# Touch_Slider.net
KiCad netlist of a schematic drawn in Altium Designer
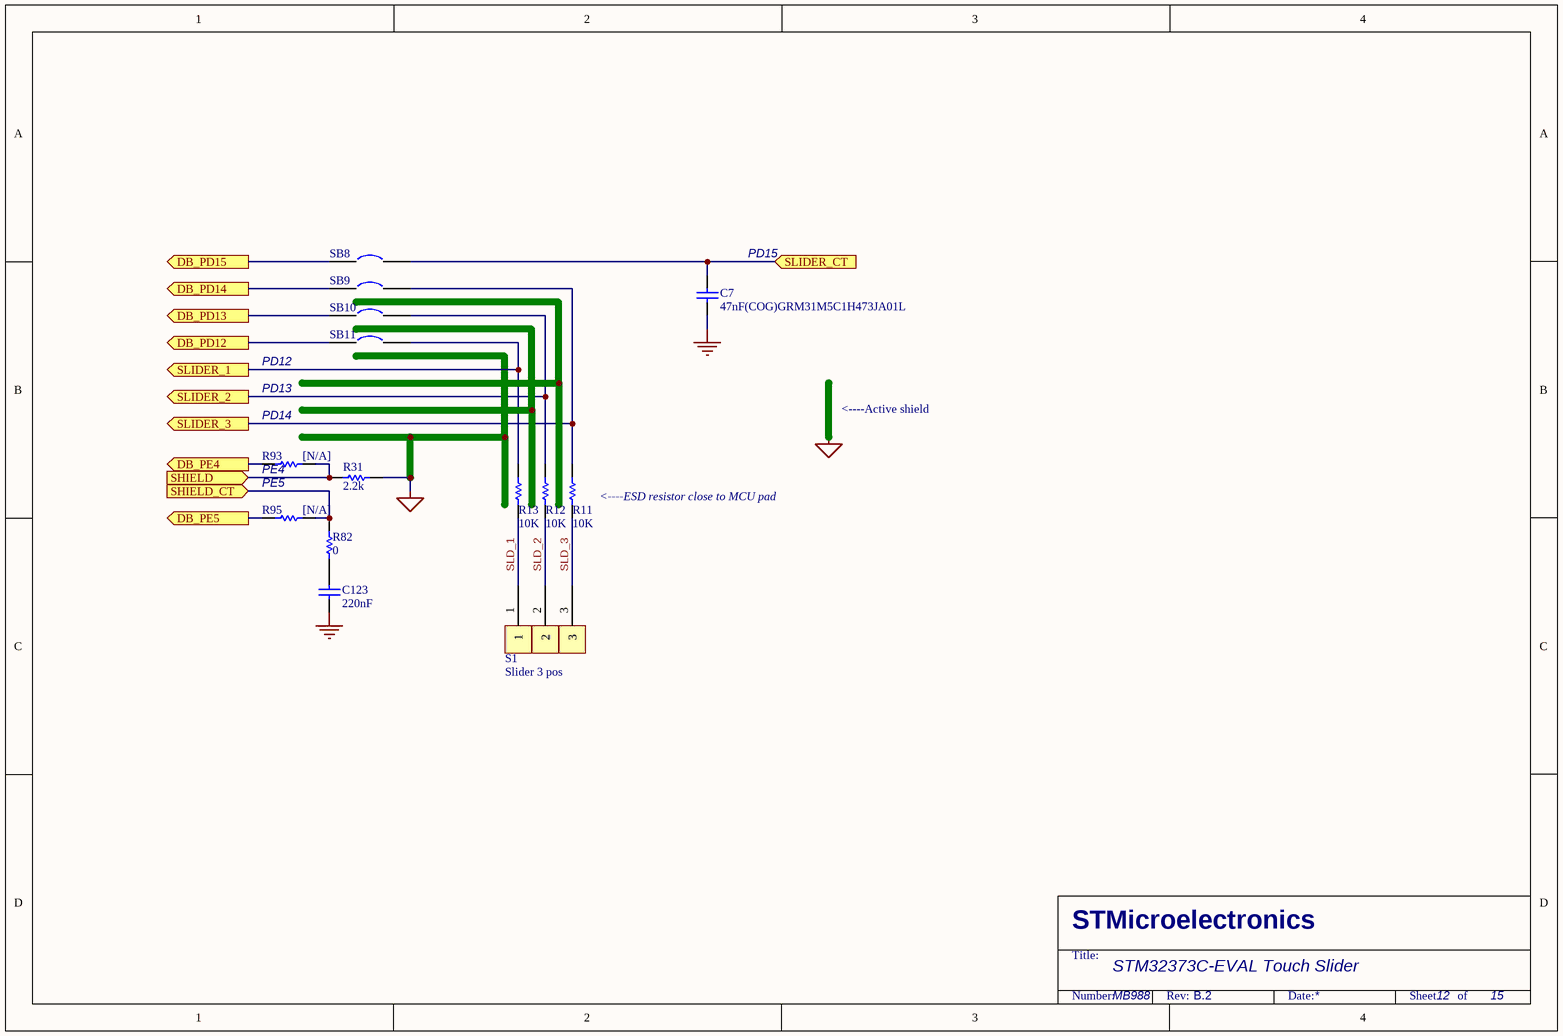
[diagram p0: Touch Slider.SchDoc]

(export (version "E")
  (design (tool "Eeschema 10.0.6"))
  (components
    (comp (ref "C7")
      (value "47nF(COG)GRM31M5C1H473JA01L")
      (footprint "1206C")
      (description "Capacitor")
      (fields (field (name "PUBLISHER") "Altium Limited"))
      (libsource (lib "Miscellaneous Devices") (part "CAP"))
    )
    (comp (ref "C123")
      (value "220nF")
      (footprint "0603C")
      (description "Capacitor")
      (fields (field (name "PUBLISHER") "Altium Limited"))
      (libsource (lib "Miscellaneous Devices") (part "CAP"))
    )
    (comp (ref "R11")
      (value "10K")
      (footprint "0603R")
      (description "Resistor")
      (fields (field (name "PUBLISHER") "Altium Limited"))
      (libsource (lib "Miscellaneous Devices") (part "res1"))
    )
    (comp (ref "R12")
      (value "10K")
      (footprint "0603R")
      (description "Resistor")
      (fields (field (name "PUBLISHER") "Altium Limited"))
      (libsource (lib "Miscellaneous Devices") (part "res1"))
    )
    (comp (ref "R13")
      (value "10K")
      (footprint "0603R")
      (description "Resistor")
      (fields (field (name "PUBLISHER") "Altium Limited"))
      (libsource (lib "Miscellaneous Devices") (part "res1"))
    )
    (comp (ref "R31")
      (value "2.2k")
      (footprint "0603R")
      (description "Resistor")
      (fields (field (name "PUBLISHER") "Altium Limited"))
      (libsource (lib "Miscellaneous Devices") (part "Res1"))
    )
    (comp (ref "R82")
      (value "0")
      (footprint "0603R")
      (description "Resistor")
      (fields (field (name "PUBLISHER") "Altium Limited"))
      (libsource (lib "Miscellaneous Devices") (part "Res1"))
    )
    (comp (ref "R93")
      (value "[N/A]")
      (footprint "0603R")
      (description "Resistor")
      (fields (field (name "PUBLISHER") "Altium Limited"))
      (libsource (lib "Miscellaneous Devices") (part "Res1"))
    )
    (comp (ref "R95")
      (value "[N/A]")
      (footprint "0603R")
      (description "Resistor")
      (fields (field (name "PUBLISHER") "Altium Limited"))
      (libsource (lib "Miscellaneous Devices") (part "Res1"))
    )
    (comp (ref "S1")
      (value "Slider 3 pos")
      (footprint "SLIDER3-2(50)")
      (description "plan de cuivre recouvert de vernis")
      (libsource (lib "MB963_1") (part "Slider 3 pos"))
    )
    (comp (ref "SB8")
      (value "~")
      (footprint "JP2_SMD")
      (description "Circuit Breaker")
      (fields (field (name "PUBLISHER") "Altium Limited"))
      (libsource (lib "Miscellaneous Devices") (part "Circuit Breaker"))
    )
    (comp (ref "SB9")
      (value "~")
      (footprint "JP2_SMD")
      (description "Circuit Breaker")
      (fields (field (name "PUBLISHER") "Altium Limited"))
      (libsource (lib "Miscellaneous Devices") (part "Circuit Breaker"))
    )
    (comp (ref "SB10")
      (value "~")
      (footprint "JP2_SMD")
      (description "Circuit Breaker")
      (fields (field (name "PUBLISHER") "Altium Limited"))
      (libsource (lib "Miscellaneous Devices") (part "Circuit Breaker"))
    )
    (comp (ref "SB11")
      (value "~")
      (footprint "JP2_SMD")
      (description "Circuit Breaker")
      (fields (field (name "PUBLISHER") "Altium Limited"))
      (libsource (lib "Miscellaneous Devices") (part "Circuit Breaker"))
    )
  )
  (nets
    (net (code "1") (name "/DB_PD12") (class "Default")
      (node (ref "SB11") (pin "1") (pinfunction "1_1") (pintype "passive"))
    )
    (net (code "2") (name "/DB_PD13") (class "Default")
      (node (ref "SB10") (pin "1") (pinfunction "1_1") (pintype "passive"))
    )
    (net (code "3") (name "/DB_PD14") (class "Default")
      (node (ref "SB9") (pin "1") (pinfunction "1_1") (pintype "passive"))
    )
    (net (code "4") (name "/DB_PD15") (class "Default")
      (node (ref "SB8") (pin "1") (pinfunction "1_1") (pintype "passive"))
    )
    (net (code "5") (name "/DB_PE4") (class "Default")
      (node (ref "R93") (pin "2") (pinfunction "2_2") (pintype "passive"))
    )
    (net (code "6") (name "/DB_PE5") (class "Default")
      (node (ref "R95") (pin "2") (pinfunction "2_2") (pintype "passive"))
    )
    (net (code "7") (name "/SHIELD") (class "Default")
      (node (ref "R31") (pin "1") (pinfunction "1_1") (pintype "passive"))
      (node (ref "R93") (pin "1") (pinfunction "1_1") (pintype "passive"))
    )
    (net (code "8") (name "/SHIELD_CT") (class "Default")
      (node (ref "R82") (pin "1") (pinfunction "1_1") (pintype "passive"))
      (node (ref "R95") (pin "1") (pinfunction "1_1") (pintype "passive"))
    )
    (net (code "9") (name "/SLD_1") (class "Default")
      (node (ref "R13") (pin "2") (pinfunction "2_2") (pintype "passive"))
      (node (ref "S1") (pin "1") (pinfunction "1_1") (pintype "passive"))
    )
    (net (code "10") (name "/SLD_2") (class "Default")
      (node (ref "R12") (pin "2") (pinfunction "2_2") (pintype "passive"))
      (node (ref "S1") (pin "2") (pinfunction "2_2") (pintype "passive"))
    )
    (net (code "11") (name "/SLD_3") (class "Default")
      (node (ref "R11") (pin "2") (pinfunction "2_2") (pintype "passive"))
      (node (ref "S1") (pin "3") (pinfunction "3_3") (pintype "passive"))
    )
    (net (code "12") (name "/SLIDER_1") (class "Default")
      (node (ref "R13") (pin "1") (pinfunction "1_1") (pintype "passive"))
      (node (ref "SB11") (pin "2") (pinfunction "2_2") (pintype "passive"))
    )
    (net (code "13") (name "/SLIDER_2") (class "Default")
      (node (ref "R12") (pin "1") (pinfunction "1_1") (pintype "passive"))
      (node (ref "SB10") (pin "2") (pinfunction "2_2") (pintype "passive"))
    )
    (net (code "14") (name "/SLIDER_3") (class "Default")
      (node (ref "R11") (pin "1") (pinfunction "1_1") (pintype "passive"))
      (node (ref "SB9") (pin "2") (pinfunction "2_2") (pintype "passive"))
    )
    (net (code "15") (name "/SLIDER_CT") (class "Default")
      (node (ref "C7") (pin "2") (pinfunction "2_2") (pintype "passive"))
      (node (ref "SB8") (pin "2") (pinfunction "2_2") (pintype "passive"))
    )
    (net (code "16") (name "GND") (class "Default")
      (node (ref "C123") (pin "1") (pinfunction "1_1") (pintype "passive"))
      (node (ref "C7") (pin "1") (pinfunction "1_1") (pintype "passive"))
    )
    (net (code "17") (name "Net-(C123-Pad2)") (class "Default")
      (node (ref "C123") (pin "2") (pinfunction "2_2") (pintype "passive"))
      (node (ref "R82") (pin "2") (pinfunction "2_2") (pintype "passive"))
    )
    (net (code "18") (name "TS_SHIELD") (class "Default")
      (node (ref "R31") (pin "2") (pinfunction "2_2") (pintype "passive"))
    )
  )
)
